# GoPro_Actuator_LED.net
KiCad netlist of a schematic drawn in Altium Designer
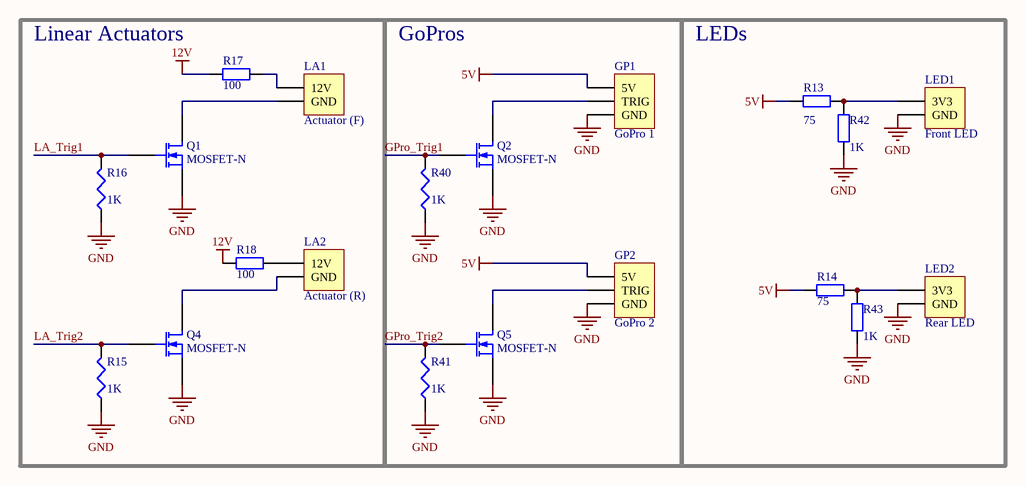
[diagram p0: GoPro_Actuator_LED.SchDoc]

(export (version "E")
  (design (tool "Eeschema 10.0.6"))
  (components
    (comp (ref "GP1")
      (value "GoPro 1")
      (footprint "HDR1X3")
      (description "Header, 3-Pin")
      (fields (field (name "PUBLISHER") "Altium Limited"))
      (libsource (lib "Miscellaneous Connectors") (part "Header 3"))
    )
    (comp (ref "GP2")
      (value "GoPro 2")
      (footprint "HDR1X3")
      (description "Header, 3-Pin")
      (fields (field (name "PUBLISHER") "Altium Limited"))
      (libsource (lib "Miscellaneous Connectors") (part "Header 3"))
    )
    (comp (ref "LA1")
      (value "Actuator (F)")
      (footprint "HDR1X2")
      (description "Header, 2-Pin")
      (fields (field (name "PUBLISHER") "Altium Limited"))
      (libsource (lib "Miscellaneous Connectors") (part "Header 2"))
    )
    (comp (ref "LA2")
      (value "Actuator (R)")
      (footprint "HDR1X2")
      (description "Header, 2-Pin")
      (fields (field (name "PUBLISHER") "Altium Limited"))
      (libsource (lib "Miscellaneous Connectors") (part "Header 2"))
    )
    (comp (ref "LED1")
      (value "Front LED")
      (footprint "HDR1X2")
      (description "Header, 2-Pin")
      (fields (field (name "PUBLISHER") "Altium Limited"))
      (libsource (lib "Miscellaneous Connectors") (part "Header 2"))
    )
    (comp (ref "LED2")
      (value "Rear LED")
      (footprint "HDR1X2")
      (description "Header, 2-Pin")
      (fields (field (name "PUBLISHER") "Altium Limited"))
      (libsource (lib "Miscellaneous Connectors") (part "Header 2"))
    )
    (comp (ref "Q1")
      (value "MOSFET-N")
      (footprint "E3")
      (description "N-Channel MOSFET")
      (fields (field (name "PUBLISHER") "Altium Limited"))
      (libsource (lib "Miscellaneous Devices") (part "MOSFET-N"))
    )
    (comp (ref "Q2")
      (value "MOSFET-N")
      (footprint "E3")
      (description "N-Channel MOSFET")
      (fields (field (name "PUBLISHER") "Altium Limited"))
      (libsource (lib "Miscellaneous Devices") (part "MOSFET-N"))
    )
    (comp (ref "Q4")
      (value "MOSFET-N")
      (footprint "E3")
      (description "N-Channel MOSFET")
      (fields (field (name "PUBLISHER") "Altium Limited"))
      (libsource (lib "Miscellaneous Devices") (part "MOSFET-N"))
    )
    (comp (ref "Q5")
      (value "MOSFET-N")
      (footprint "E3")
      (description "N-Channel MOSFET")
      (fields (field (name "PUBLISHER") "Altium Limited"))
      (libsource (lib "Miscellaneous Devices") (part "MOSFET-N"))
    )
    (comp (ref "R13")
      (value "75")
      (footprint "AXIAL-0.4")
      (description "Resistor")
      (fields (field (name "Comment") "Res2") (field (name "PUBLISHER") "Altium Limited"))
      (libsource (lib "Miscellaneous Devices") (part "Res2"))
    )
    (comp (ref "R14")
      (value "75")
      (footprint "AXIAL-0.4")
      (description "Resistor")
      (fields (field (name "Comment") "Res2") (field (name "PUBLISHER") "Altium Limited"))
      (libsource (lib "Miscellaneous Devices") (part "Res2"))
    )
    (comp (ref "R15")
      (value "1K")
      (footprint "J1-0603")
      (description "Resistor")
      (fields (field (name "PUBLISHER") "Altium Limited"))
      (libsource (lib "Miscellaneous Devices") (part "Res3"))
    )
    (comp (ref "R16")
      (value "1K")
      (footprint "J1-0603")
      (description "Resistor")
      (fields (field (name "PUBLISHER") "Altium Limited"))
      (libsource (lib "Miscellaneous Devices") (part "Res3"))
    )
    (comp (ref "R17")
      (value "100")
      (footprint "AXIAL-0.4")
      (description "Resistor")
      (fields (field (name "Comment") "Res2") (field (name "PUBLISHER") "Altium Limited"))
      (libsource (lib "") (part "Res2_1"))
    )
    (comp (ref "R18")
      (value "100")
      (footprint "AXIAL-0.4")
      (description "Resistor")
      (fields (field (name "Comment") "Res2") (field (name "PUBLISHER") "Altium Limited"))
      (libsource (lib "") (part "Res2_1"))
    )
    (comp (ref "R40")
      (value "1K")
      (footprint "J1-0603")
      (description "Resistor")
      (fields (field (name "PUBLISHER") "Altium Limited"))
      (libsource (lib "Miscellaneous Devices") (part "Res3"))
    )
    (comp (ref "R41")
      (value "1K")
      (footprint "J1-0603")
      (description "Resistor")
      (fields (field (name "PUBLISHER") "Altium Limited"))
      (libsource (lib "Miscellaneous Devices") (part "Res3"))
    )
    (comp (ref "R42")
      (value "1K")
      (footprint "AXIAL-0.4")
      (description "Resistor")
      (fields (field (name "Comment") "Res2") (field (name "PUBLISHER") "Altium Limited"))
      (libsource (lib "") (part "Res2_2"))
    )
    (comp (ref "R43")
      (value "1K")
      (footprint "AXIAL-0.4")
      (description "Resistor")
      (fields (field (name "Comment") "Res2") (field (name "PUBLISHER") "Altium Limited"))
      (libsource (lib "Miscellaneous Devices") (part "Res2"))
    )
  )
  (nets
    (net (code "1") (name "/GPro_Trig1") (class "Default")
      (node (ref "Q2") (pin "2") (pinfunction "G_2") (pintype "passive"))
      (node (ref "R40") (pin "2") (pinfunction "2_2") (pintype "passive"))
    )
    (net (code "2") (name "/GPro_Trig2") (class "Default")
      (node (ref "Q5") (pin "2") (pinfunction "G_2") (pintype "passive"))
      (node (ref "R41") (pin "2") (pinfunction "2_2") (pintype "passive"))
    )
    (net (code "3") (name "/LA_Trig1") (class "Default")
      (node (ref "Q1") (pin "2") (pinfunction "G_2") (pintype "passive"))
      (node (ref "R16") (pin "2") (pinfunction "2_2") (pintype "passive"))
    )
    (net (code "4") (name "/LA_Trig2") (class "Default")
      (node (ref "Q4") (pin "2") (pinfunction "G_2") (pintype "passive"))
      (node (ref "R15") (pin "2") (pinfunction "2_2") (pintype "passive"))
    )
    (net (code "5") (name "5V") (class "Default")
      (node (ref "GP1") (pin "1") (pinfunction "5V_1") (pintype "passive"))
      (node (ref "GP2") (pin "1") (pinfunction "5V_1") (pintype "passive"))
      (node (ref "R13") (pin "2") (pinfunction "2_2") (pintype "passive"))
      (node (ref "R14") (pin "2") (pinfunction "2_2") (pintype "passive"))
    )
    (net (code "6") (name "12V") (class "Default")
      (node (ref "R17") (pin "1") (pinfunction "1_1") (pintype "passive"))
      (node (ref "R18") (pin "1") (pinfunction "1_1") (pintype "passive"))
    )
    (net (code "7") (name "GND") (class "Default")
      (node (ref "GP1") (pin "3") (pinfunction "GND_3") (pintype "passive"))
      (node (ref "GP2") (pin "3") (pinfunction "GND_3") (pintype "passive"))
      (node (ref "LED1") (pin "2") (pinfunction "GND_2") (pintype "passive"))
      (node (ref "LED2") (pin "2") (pinfunction "GND_2") (pintype "passive"))
      (node (ref "Q1") (pin "3") (pinfunction "S_3") (pintype "passive"))
      (node (ref "Q2") (pin "3") (pinfunction "S_3") (pintype "passive"))
      (node (ref "Q4") (pin "3") (pinfunction "S_3") (pintype "passive"))
      (node (ref "Q5") (pin "3") (pinfunction "S_3") (pintype "passive"))
      (node (ref "R15") (pin "1") (pinfunction "1_1") (pintype "passive"))
      (node (ref "R16") (pin "1") (pinfunction "1_1") (pintype "passive"))
      (node (ref "R40") (pin "1") (pinfunction "1_1") (pintype "passive"))
      (node (ref "R41") (pin "1") (pinfunction "1_1") (pintype "passive"))
      (node (ref "R42") (pin "1") (pinfunction "1_1") (pintype "passive"))
      (node (ref "R43") (pin "2") (pinfunction "2_2") (pintype "passive"))
    )
    (net (code "8") (name "Net-(GP1-TRIG)") (class "Default")
      (node (ref "GP1") (pin "2") (pinfunction "TRIG_2") (pintype "passive"))
      (node (ref "Q2") (pin "1") (pinfunction "D_1") (pintype "passive"))
    )
    (net (code "9") (name "Net-(GP2-TRIG)") (class "Default")
      (node (ref "GP2") (pin "2") (pinfunction "TRIG_2") (pintype "passive"))
      (node (ref "Q5") (pin "1") (pinfunction "D_1") (pintype "passive"))
    )
    (net (code "10") (name "Net-(LA1-12V)") (class "Default")
      (node (ref "LA1") (pin "1") (pinfunction "12V_1") (pintype "passive"))
      (node (ref "R17") (pin "2") (pinfunction "2_2") (pintype "passive"))
    )
    (net (code "11") (name "Net-(LA1-GND)") (class "Default")
      (node (ref "LA1") (pin "2") (pinfunction "GND_2") (pintype "passive"))
      (node (ref "Q1") (pin "1") (pinfunction "D_1") (pintype "passive"))
    )
    (net (code "12") (name "Net-(LA2-12V)") (class "Default")
      (node (ref "LA2") (pin "1") (pinfunction "12V_1") (pintype "passive"))
      (node (ref "R18") (pin "2") (pinfunction "2_2") (pintype "passive"))
    )
    (net (code "13") (name "Net-(LA2-GND)") (class "Default")
      (node (ref "LA2") (pin "2") (pinfunction "GND_2") (pintype "passive"))
      (node (ref "Q4") (pin "1") (pinfunction "D_1") (pintype "passive"))
    )
    (net (code "14") (name "Net-(LED1-12V)") (class "Default")
      (node (ref "LED1") (pin "1") (pinfunction "12V_1") (pintype "passive"))
      (node (ref "R13") (pin "1") (pinfunction "1_1") (pintype "passive"))
      (node (ref "R42") (pin "2") (pinfunction "2_2") (pintype "passive"))
    )
    (net (code "15") (name "Net-(LED2-12V)") (class "Default")
      (node (ref "LED2") (pin "1") (pinfunction "12V_1") (pintype "passive"))
      (node (ref "R14") (pin "1") (pinfunction "1_1") (pintype "passive"))
      (node (ref "R43") (pin "1") (pinfunction "1_1") (pintype "passive"))
    )
  )
)
